# PowerModule_Schematic.net
KiCad netlist of a schematic drawn in Altium Designer
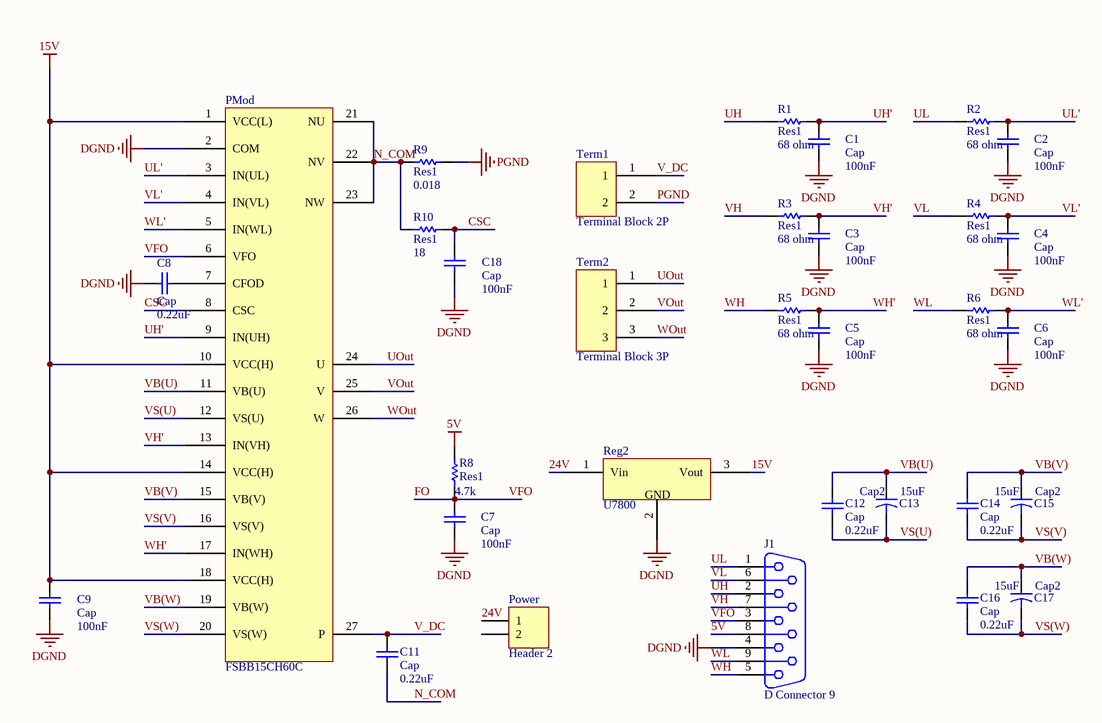
[diagram p0: PowerModule_Schematic.SchDoc]

(export (version "E")
  (design (tool "Eeschema 10.0.6"))
  (components
    (comp (ref "C1")
      (value "Cap")
      (footprint "NPolar_Cap")
      (description "Capacitor")
      (fields (field (name "ALTIUM_VALUE") "100nF") (field (name "PUBLISHER") "Altium Limited"))
      (libsource (lib "Miscellaneous Devices") (part "Cap"))
    )
    (comp (ref "C2")
      (value "Cap")
      (footprint "NPolar_Cap")
      (description "Capacitor")
      (fields (field (name "ALTIUM_VALUE") "100nF") (field (name "PUBLISHER") "Altium Limited"))
      (libsource (lib "Miscellaneous Devices") (part "Cap"))
    )
    (comp (ref "C3")
      (value "Cap")
      (footprint "NPolar_Cap")
      (description "Capacitor")
      (fields (field (name "ALTIUM_VALUE") "100nF") (field (name "PUBLISHER") "Altium Limited"))
      (libsource (lib "Miscellaneous Devices") (part "Cap"))
    )
    (comp (ref "C4")
      (value "Cap")
      (footprint "NPolar_Cap")
      (description "Capacitor")
      (fields (field (name "ALTIUM_VALUE") "100nF") (field (name "PUBLISHER") "Altium Limited"))
      (libsource (lib "Miscellaneous Devices") (part "Cap"))
    )
    (comp (ref "C5")
      (value "Cap")
      (footprint "NPolar_Cap")
      (description "Capacitor")
      (fields (field (name "ALTIUM_VALUE") "100nF") (field (name "PUBLISHER") "Altium Limited"))
      (libsource (lib "Miscellaneous Devices") (part "Cap"))
    )
    (comp (ref "C6")
      (value "Cap")
      (footprint "NPolar_Cap")
      (description "Capacitor")
      (fields (field (name "ALTIUM_VALUE") "100nF") (field (name "PUBLISHER") "Altium Limited"))
      (libsource (lib "Miscellaneous Devices") (part "Cap"))
    )
    (comp (ref "C7")
      (value "Cap")
      (footprint "NPolar_Cap")
      (description "Capacitor")
      (fields (field (name "ALTIUM_VALUE") "100nF") (field (name "PUBLISHER") "Altium Limited"))
      (libsource (lib "Miscellaneous Devices") (part "Cap"))
    )
    (comp (ref "C8")
      (value "Cap")
      (footprint "NPolar_Cap")
      (description "Capacitor")
      (fields (field (name "ALTIUM_VALUE") "0.22uF") (field (name "PUBLISHER") "Altium Limited"))
      (libsource (lib "Miscellaneous Devices") (part "Cap"))
    )
    (comp (ref "C9")
      (value "Cap")
      (footprint "NPolar_Cap")
      (description "Capacitor")
      (fields (field (name "ALTIUM_VALUE") "100nF") (field (name "PUBLISHER") "Altium Limited"))
      (libsource (lib "Miscellaneous Devices") (part "Cap"))
    )
    (comp (ref "C11")
      (value "Cap")
      (footprint "NPolar_Cap")
      (description "Capacitor")
      (fields (field (name "ALTIUM_VALUE") "0.22uF") (field (name "PUBLISHER") "Altium Limited"))
      (libsource (lib "Miscellaneous Devices") (part "Cap"))
    )
    (comp (ref "C12")
      (value "Cap")
      (footprint "NPolar_Cap")
      (description "Capacitor")
      (fields (field (name "ALTIUM_VALUE") "0.22uF") (field (name "PUBLISHER") "Altium Limited"))
      (libsource (lib "Miscellaneous Devices") (part "Cap"))
    )
    (comp (ref "C13")
      (value "Cap2")
      (footprint "Polar_Cap")
      (description "Capacitor")
      (fields (field (name "ALTIUM_VALUE") "15uF") (field (name "PUBLISHER") "Altium Limited"))
      (libsource (lib "Miscellaneous Devices") (part "Cap2"))
    )
    (comp (ref "C14")
      (value "Cap")
      (footprint "NPolar_Cap")
      (description "Capacitor")
      (fields (field (name "ALTIUM_VALUE") "0.22uF") (field (name "PUBLISHER") "Altium Limited"))
      (libsource (lib "Miscellaneous Devices") (part "Cap"))
    )
    (comp (ref "C15")
      (value "Cap2")
      (footprint "Polar_Cap")
      (description "Capacitor")
      (fields (field (name "ALTIUM_VALUE") "15uF") (field (name "PUBLISHER") "Altium Limited"))
      (libsource (lib "Miscellaneous Devices") (part "Cap2"))
    )
    (comp (ref "C16")
      (value "Cap")
      (footprint "NPolar_Cap")
      (description "Capacitor")
      (fields (field (name "ALTIUM_VALUE") "0.22uF") (field (name "PUBLISHER") "Altium Limited"))
      (libsource (lib "Miscellaneous Devices") (part "Cap"))
    )
    (comp (ref "C17")
      (value "Cap2")
      (footprint "Polar_Cap")
      (description "Capacitor")
      (fields (field (name "ALTIUM_VALUE") "15uF") (field (name "PUBLISHER") "Altium Limited"))
      (libsource (lib "Miscellaneous Devices") (part "Cap2"))
    )
    (comp (ref "C18")
      (value "Cap")
      (footprint "NPolar_Cap")
      (description "Capacitor")
      (fields (field (name "ALTIUM_VALUE") "100nF") (field (name "PUBLISHER") "Altium Limited"))
      (libsource (lib "Miscellaneous Devices") (part "Cap"))
    )
    (comp (ref "J1")
      (value "D Connector 9")
      (footprint "DSUB1.385-2H9")
      (description "Receptacle Assembly, 9 Position, Right Angle")
      (fields (field (name "PUBLISHER") "Altium Limited"))
      (libsource (lib "MyBoard_v1") (part "D Connector 9"))
    )
    (comp (ref "PMod")
      (value "FSBB15CH60C")
      (footprint "FYP:FSBB20CH60F")
      (libsource (lib "MyBoard_v1") (part "FSBB15CH60C"))
    )
    (comp (ref "Power")
      (value "Header 2")
      (footprint "HDR1X2")
      (description "Header, 2-Pin")
      (fields (field (name "PUBLISHER") "Altium Limited"))
      (libsource (lib "Miscellaneous Connectors") (part "Header 2"))
    )
    (comp (ref "R1")
      (value "Res1")
      (footprint "AXIAL-0.3")
      (description "Resistor")
      (fields (field (name "ALTIUM_VALUE") "68 ohm") (field (name "PUBLISHER") "Altium Limited"))
      (libsource (lib "Miscellaneous Devices") (part "Res1"))
    )
    (comp (ref "R2")
      (value "Res1")
      (footprint "AXIAL-0.3")
      (description "Resistor")
      (fields (field (name "ALTIUM_VALUE") "68 ohm") (field (name "PUBLISHER") "Altium Limited"))
      (libsource (lib "Miscellaneous Devices") (part "Res1"))
    )
    (comp (ref "R3")
      (value "Res1")
      (footprint "AXIAL-0.3")
      (description "Resistor")
      (fields (field (name "ALTIUM_VALUE") "68 ohm") (field (name "PUBLISHER") "Altium Limited"))
      (libsource (lib "Miscellaneous Devices") (part "Res1"))
    )
    (comp (ref "R4")
      (value "Res1")
      (footprint "AXIAL-0.3")
      (description "Resistor")
      (fields (field (name "ALTIUM_VALUE") "68 ohm") (field (name "PUBLISHER") "Altium Limited"))
      (libsource (lib "Miscellaneous Devices") (part "Res1"))
    )
    (comp (ref "R5")
      (value "Res1")
      (footprint "AXIAL-0.3")
      (description "Resistor")
      (fields (field (name "ALTIUM_VALUE") "68 ohm") (field (name "PUBLISHER") "Altium Limited"))
      (libsource (lib "Miscellaneous Devices") (part "Res1"))
    )
    (comp (ref "R6")
      (value "Res1")
      (footprint "AXIAL-0.3")
      (description "Resistor")
      (fields (field (name "ALTIUM_VALUE") "68 ohm") (field (name "PUBLISHER") "Altium Limited"))
      (libsource (lib "Miscellaneous Devices") (part "Res1"))
    )
    (comp (ref "R8")
      (value "Res1")
      (footprint "AXIAL-0.3")
      (description "Resistor")
      (fields (field (name "ALTIUM_VALUE") "4.7k") (field (name "PUBLISHER") "Altium Limited"))
      (libsource (lib "Miscellaneous Devices") (part "Res1"))
    )
    (comp (ref "R9")
      (value "Res1")
      (footprint "AXIAL-0.3")
      (description "Resistor")
      (fields (field (name "ALTIUM_VALUE") "0.018") (field (name "PUBLISHER") "Altium Limited"))
      (libsource (lib "Miscellaneous Devices") (part "Res1"))
    )
    (comp (ref "R10")
      (value "Res1")
      (footprint "AXIAL-0.3")
      (description "Resistor")
      (fields (field (name "ALTIUM_VALUE") "18") (field (name "PUBLISHER") "Altium Limited"))
      (libsource (lib "Miscellaneous Devices") (part "Res1"))
    )
    (comp (ref "Reg2") (value "U7800") (footprint "FYP:U7800") (libsource (lib "MyBoard_v1") (part "U7800")))
    (comp (ref "Term1")
      (value "Terminal Block 2P")
      (footprint "Terminal Block 2 Pin")
      (libsource (lib "MyBoard_v1") (part "Terminal Block 2P"))
    )
    (comp (ref "Term2")
      (value "Terminal Block 3P")
      (footprint "Terminal Block 3 Pin")
      (libsource (lib "MyBoard_v1") (part "Terminal Block 3P"))
    )
  )
  (nets
    (net (code "1") (name "/24V") (class "Default")
      (node (ref "Power") (pin "1") (pinfunction "1_1") (pintype "passive"))
      (node (ref "Reg2") (pin "1") (pinfunction "Vin_1") (pintype "passive"))
    )
    (net (code "2") (name "/CSC") (class "Default")
      (node (ref "C18") (pin "2") (pinfunction "2_2") (pintype "passive"))
      (node (ref "PMod") (pin "8") (pinfunction "CSC_8") (pintype "passive"))
      (node (ref "R10") (pin "1") (pinfunction "1_1") (pintype "passive"))
    )
    (net (code "3") (name "/FO") (class "Default")
      (node (ref "C7") (pin "2") (pinfunction "2_2") (pintype "passive"))
      (node (ref "J1") (pin "3") (pinfunction "3_3") (pintype "passive"))
      (node (ref "PMod") (pin "6") (pinfunction "VFO_6") (pintype "passive"))
      (node (ref "R8") (pin "1") (pinfunction "1_1") (pintype "passive"))
    )
    (net (code "4") (name "/N_COM") (class "Default")
      (node (ref "C11") (pin "1") (pinfunction "1_1") (pintype "passive"))
      (node (ref "PMod") (pin "21") (pinfunction "NU_21") (pintype "passive"))
      (node (ref "PMod") (pin "22") (pinfunction "NV_22") (pintype "passive"))
      (node (ref "PMod") (pin "23") (pinfunction "NW_23") (pintype "passive"))
      (node (ref "R10") (pin "2") (pinfunction "2_2") (pintype "passive"))
      (node (ref "R9") (pin "2") (pinfunction "2_2") (pintype "passive"))
    )
    (net (code "5") (name "/UH") (class "Default")
      (node (ref "J1") (pin "2") (pinfunction "2_2") (pintype "passive"))
      (node (ref "R1") (pin "1") (pinfunction "1_1") (pintype "passive"))
    )
    (net (code "6") (name "/UH'") (class "Default")
      (node (ref "C1") (pin "2") (pinfunction "2_2") (pintype "passive"))
      (node (ref "PMod") (pin "9") (pinfunction "IN(UH)_9") (pintype "passive"))
      (node (ref "R1") (pin "2") (pinfunction "2_2") (pintype "passive"))
    )
    (net (code "7") (name "/UL") (class "Default")
      (node (ref "J1") (pin "1") (pinfunction "1_1") (pintype "passive"))
      (node (ref "R2") (pin "1") (pinfunction "1_1") (pintype "passive"))
    )
    (net (code "8") (name "/UL'") (class "Default")
      (node (ref "C2") (pin "2") (pinfunction "2_2") (pintype "passive"))
      (node (ref "PMod") (pin "3") (pinfunction "IN(UL)_3") (pintype "passive"))
      (node (ref "R2") (pin "2") (pinfunction "2_2") (pintype "passive"))
    )
    (net (code "9") (name "/UOut") (class "Default")
      (node (ref "PMod") (pin "24") (pinfunction "U_24") (pintype "passive"))
      (node (ref "Term2") (pin "1") (pinfunction "1_1") (pintype "passive"))
    )
    (net (code "10") (name "/VB(U)") (class "Default")
      (node (ref "C12") (pin "2") (pinfunction "2_2") (pintype "passive"))
      (node (ref "C13") (pin "1") (pinfunction "1_1") (pintype "passive"))
      (node (ref "PMod") (pin "11") (pinfunction "VB(U)_11") (pintype "passive"))
    )
    (net (code "11") (name "/VB(V)") (class "Default")
      (node (ref "C14") (pin "2") (pinfunction "2_2") (pintype "passive"))
      (node (ref "C15") (pin "1") (pinfunction "1_1") (pintype "passive"))
      (node (ref "PMod") (pin "15") (pinfunction "VB(V)_15") (pintype "passive"))
    )
    (net (code "12") (name "/VB(W)") (class "Default")
      (node (ref "C16") (pin "2") (pinfunction "2_2") (pintype "passive"))
      (node (ref "C17") (pin "1") (pinfunction "1_1") (pintype "passive"))
      (node (ref "PMod") (pin "19") (pinfunction "VB(W)_19") (pintype "passive"))
    )
    (net (code "13") (name "/VH") (class "Default")
      (node (ref "J1") (pin "7") (pinfunction "7_7") (pintype "passive"))
      (node (ref "R3") (pin "1") (pinfunction "1_1") (pintype "passive"))
    )
    (net (code "14") (name "/VH'") (class "Default")
      (node (ref "C3") (pin "2") (pinfunction "2_2") (pintype "passive"))
      (node (ref "PMod") (pin "13") (pinfunction "IN(VH)_13") (pintype "passive"))
      (node (ref "R3") (pin "2") (pinfunction "2_2") (pintype "passive"))
    )
    (net (code "15") (name "/VL") (class "Default")
      (node (ref "J1") (pin "6") (pinfunction "6_6") (pintype "passive"))
      (node (ref "R4") (pin "1") (pinfunction "1_1") (pintype "passive"))
    )
    (net (code "16") (name "/VL'") (class "Default")
      (node (ref "C4") (pin "2") (pinfunction "2_2") (pintype "passive"))
      (node (ref "PMod") (pin "4") (pinfunction "IN(VL)_4") (pintype "passive"))
      (node (ref "R4") (pin "2") (pinfunction "2_2") (pintype "passive"))
    )
    (net (code "17") (name "/VOut") (class "Default")
      (node (ref "PMod") (pin "25") (pinfunction "V_25") (pintype "passive"))
      (node (ref "Term2") (pin "2") (pinfunction "2_2") (pintype "passive"))
    )
    (net (code "18") (name "/VS(U)") (class "Default")
      (node (ref "C12") (pin "1") (pinfunction "1_1") (pintype "passive"))
      (node (ref "C13") (pin "2") (pinfunction "2_2") (pintype "passive"))
      (node (ref "PMod") (pin "12") (pinfunction "VS(U)_12") (pintype "passive"))
    )
    (net (code "19") (name "/VS(V)") (class "Default")
      (node (ref "C14") (pin "1") (pinfunction "1_1") (pintype "passive"))
      (node (ref "C15") (pin "2") (pinfunction "2_2") (pintype "passive"))
      (node (ref "PMod") (pin "16") (pinfunction "VS(V)_16") (pintype "passive"))
    )
    (net (code "20") (name "/VS(W)") (class "Default")
      (node (ref "C16") (pin "1") (pinfunction "1_1") (pintype "passive"))
      (node (ref "C17") (pin "2") (pinfunction "2_2") (pintype "passive"))
      (node (ref "PMod") (pin "20") (pinfunction "VS(W)_20") (pintype "passive"))
    )
    (net (code "21") (name "/V_DC") (class "Default")
      (node (ref "C11") (pin "2") (pinfunction "2_2") (pintype "passive"))
      (node (ref "PMod") (pin "27") (pinfunction "P_27") (pintype "passive"))
      (node (ref "Term1") (pin "1") (pinfunction "1_1") (pintype "passive"))
    )
    (net (code "22") (name "/WH") (class "Default")
      (node (ref "J1") (pin "5") (pinfunction "5_5") (pintype "passive"))
      (node (ref "R5") (pin "1") (pinfunction "1_1") (pintype "passive"))
    )
    (net (code "23") (name "/WH'") (class "Default")
      (node (ref "C5") (pin "2") (pinfunction "2_2") (pintype "passive"))
      (node (ref "PMod") (pin "17") (pinfunction "IN(WH)_17") (pintype "passive"))
      (node (ref "R5") (pin "2") (pinfunction "2_2") (pintype "passive"))
    )
    (net (code "24") (name "/WL") (class "Default")
      (node (ref "J1") (pin "9") (pinfunction "9_9") (pintype "passive"))
      (node (ref "R6") (pin "1") (pinfunction "1_1") (pintype "passive"))
    )
    (net (code "25") (name "/WL'") (class "Default")
      (node (ref "C6") (pin "2") (pinfunction "2_2") (pintype "passive"))
      (node (ref "PMod") (pin "5") (pinfunction "IN(WL)_5") (pintype "passive"))
      (node (ref "R6") (pin "2") (pinfunction "2_2") (pintype "passive"))
    )
    (net (code "26") (name "/WOut") (class "Default")
      (node (ref "PMod") (pin "26") (pinfunction "W_26") (pintype "passive"))
      (node (ref "Term2") (pin "3") (pinfunction "3_3") (pintype "passive"))
    )
    (net (code "27") (name "5V") (class "Default")
      (node (ref "J1") (pin "8") (pinfunction "8_8") (pintype "passive"))
      (node (ref "R8") (pin "2") (pinfunction "2_2") (pintype "passive"))
    )
    (net (code "28") (name "15V") (class "Default")
      (node (ref "C9") (pin "2") (pinfunction "2_2") (pintype "passive"))
      (node (ref "PMod") (pin "1") (pinfunction "VCC(L)_1") (pintype "passive"))
      (node (ref "PMod") (pin "10") (pinfunction "VCC(H)_10") (pintype "passive"))
      (node (ref "PMod") (pin "14") (pinfunction "VCC(H)_14") (pintype "passive"))
      (node (ref "PMod") (pin "18") (pinfunction "VCC(H)_18") (pintype "passive"))
      (node (ref "Reg2") (pin "3") (pinfunction "Vout_3") (pintype "passive"))
    )
    (net (code "29") (name "DGND") (class "Default")
      (node (ref "C1") (pin "1") (pinfunction "1_1") (pintype "passive"))
      (node (ref "C18") (pin "1") (pinfunction "1_1") (pintype "passive"))
      (node (ref "C2") (pin "1") (pinfunction "1_1") (pintype "passive"))
      (node (ref "C3") (pin "1") (pinfunction "1_1") (pintype "passive"))
      (node (ref "C4") (pin "1") (pinfunction "1_1") (pintype "passive"))
      (node (ref "C5") (pin "1") (pinfunction "1_1") (pintype "passive"))
      (node (ref "C6") (pin "1") (pinfunction "1_1") (pintype "passive"))
      (node (ref "C7") (pin "1") (pinfunction "1_1") (pintype "passive"))
      (node (ref "C8") (pin "1") (pinfunction "1_1") (pintype "passive"))
      (node (ref "C9") (pin "1") (pinfunction "1_1") (pintype "passive"))
      (node (ref "J1") (pin "4") (pinfunction "4_4") (pintype "passive"))
      (node (ref "PMod") (pin "2") (pinfunction "COM_2") (pintype "passive"))
      (node (ref "Reg2") (pin "2") (pinfunction "GND_2") (pintype "power_in"))
    )
    (net (code "30") (name "Net-(PMod-CFOD)") (class "Default")
      (node (ref "C8") (pin "2") (pinfunction "2_2") (pintype "passive"))
      (node (ref "PMod") (pin "7") (pinfunction "CFOD_7") (pintype "passive"))
    )
    (net (code "31") (name "PGND") (class "Default")
      (node (ref "R9") (pin "1") (pinfunction "1_1") (pintype "passive"))
      (node (ref "Term1") (pin "2") (pinfunction "2_2") (pintype "passive"))
    )
    (net (code "32") (name "unconnected-(Power-Pad2)") (class "Default")
      (node (ref "Power") (pin "2") (pinfunction "2_2") (pintype "passive"))
    )
  )
)
